# GAT262_LoRa_OTG.net
KiCad netlist of a schematic drawn in Altium Designer
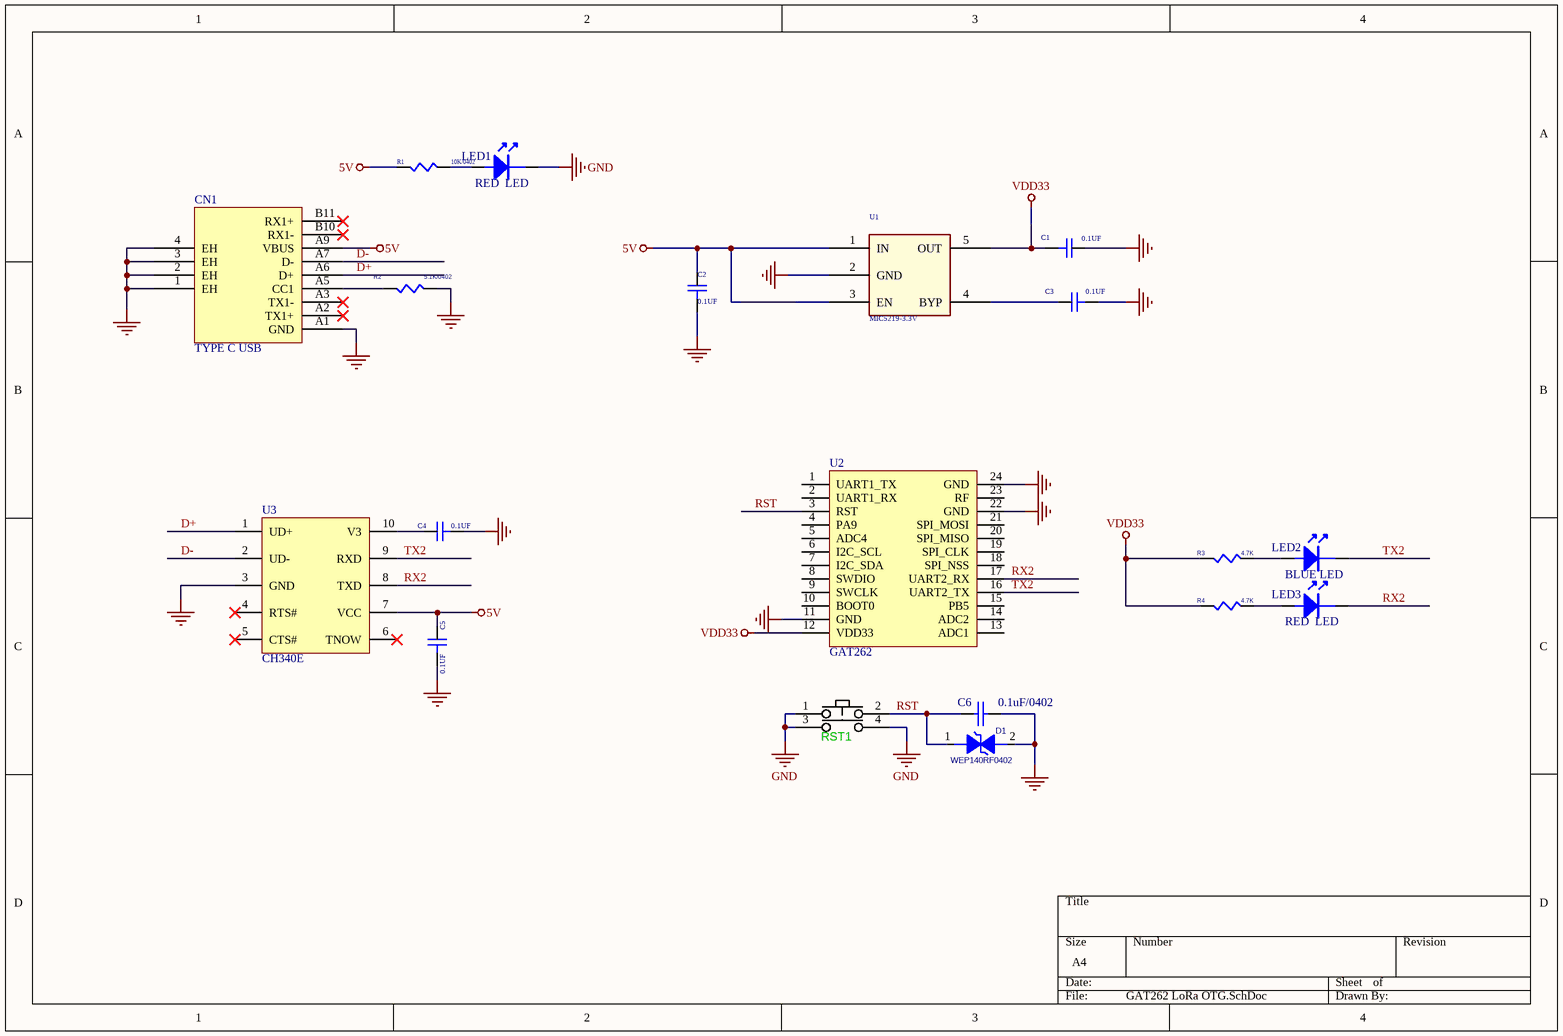
[diagram p0: GAT262 LoRa OTG.SchDoc]

(export (version "E")
  (design (tool "Eeschema 10.0.6"))
  (components
    (comp (ref "C1") (value "0.1UF") (footprint "C0402") (libsource (lib "*") (part "0_1.1UF")))
    (comp (ref "C2") (value "0.1UF") (footprint "C0402") (libsource (lib "*") (part "0_1.1UF")))
    (comp (ref "C3") (value "0.1UF") (footprint "C0402") (libsource (lib "*") (part "0_1.1UF")))
    (comp (ref "C4") (value "0.1UF") (footprint "C0402") (libsource (lib "*") (part "0_1.1UF")))
    (comp (ref "C5") (value "0.1UF") (footprint "C0402") (libsource (lib "*") (part "0_1.1UF")))
    (comp (ref "C6")
      (value "0.1uF/0402")
      (footprint "C0402")
      (description "Capacitor")
      (libsource (lib "电阻容感类") (part "CAP"))
    )
    (comp (ref "CN1")
      (value "TYPE C USB")
      (footprint "TYPE-C-9")
      (description "Type-C C2988371")
      (libsource (lib "Schlib1") (part "TYPE-C 9P"))
    )
    (comp (ref "D1")
      (value "WEP140RF0402")
      (footprint "ESD0402")
      (libsource (lib "*") (part "DIODE SCHOTTKY_1"))
    )
    (comp (ref "LED1")
      (value "RED  LED")
      (footprint "LED0603_RED_3D")
      (libsource (lib "LoRa DTU_20180911") (part "LED"))
    )
    (comp (ref "LED2")
      (value "BLUE LED")
      (footprint "LED0603_RED_3D")
      (libsource (lib "LoRa DTU_20180911") (part "LED"))
    )
    (comp (ref "LED3")
      (value "RED  LED")
      (footprint "LED0603_RED_3D")
      (libsource (lib "LoRa DTU_20180911") (part "LED"))
    )
    (comp (ref "R1") (value "10K/0402") (footprint "R0402") (libsource (lib "*") (part "R0402_1.06K_WALSIN")))
    (comp (ref "R2")
      (value "5.1K/0402")
      (footprint "R0402")
      (libsource (lib "*") (part "R0402_1.06K_WALSIN"))
    )
    (comp (ref "R3") (value "4.7K") (footprint "R0402") (libsource (lib "*") (part "R0402_1.06K_WALSIN")))
    (comp (ref "R4") (value "4.7K") (footprint "R0402") (libsource (lib "*") (part "R0402_1.06K_WALSIN")))
    (comp (ref "RST1") (value "KEY1") (footprint "SMDPUSHBUTTON4X2X3_5") (libsource (lib "*") (part "KEY1")))
    (comp (ref "U1")
      (value "MIC5219-3.3V")
      (footprint "SOT23-5")
      (libsource (lib "*") (part "REG CAT7101_2"))
    )
    (comp (ref "U2")
      (value "GAT262")
      (footprint "EVBCB-2*1.27")
      (description "2*12-1.2")
      (libsource (lib "STM32WLE5CC") (part "CONNECT_2"))
    )
    (comp (ref "U3") (value "CH340E") (footprint "CH340E") (libsource (lib "ST50H_EKB") (part "CH340E")))
  )
  (nets
    (net (code "1") (name "/D+") (class "Default")
      (node (ref "CN1") (pin "A6") (pinfunction "D+_A6") (pintype "passive"))
      (node (ref "U3") (pin "1") (pinfunction "UD+_1") (pintype "passive"))
    )
    (net (code "2") (name "/D-") (class "Default")
      (node (ref "CN1") (pin "A7") (pinfunction "D-_A7") (pintype "passive"))
      (node (ref "U3") (pin "2") (pinfunction "UD-_2") (pintype "passive"))
    )
    (net (code "3") (name "/RST") (class "Default")
      (node (ref "C6") (pin "2") (pinfunction "2_2") (pintype "passive"))
      (node (ref "D1") (pin "1") (pinfunction "ANODE_1") (pintype "passive"))
      (node (ref "RST1") (pin "2") (pinfunction "2_2") (pintype "passive"))
      (node (ref "U2") (pin "3") (pinfunction "RST_3") (pintype "passive"))
    )
    (net (code "4") (name "/RX2") (class "Default")
      (node (ref "LED3") (pin "2") (pinfunction "2_2") (pintype "passive"))
      (node (ref "U2") (pin "17") (pinfunction "UART2_RX_17") (pintype "passive"))
      (node (ref "U3") (pin "8") (pinfunction "TXD_8") (pintype "passive"))
    )
    (net (code "5") (name "/TX2") (class "Default")
      (node (ref "LED2") (pin "2") (pinfunction "2_2") (pintype "passive"))
      (node (ref "U2") (pin "16") (pinfunction "UART2_TX_16") (pintype "passive"))
      (node (ref "U3") (pin "9") (pinfunction "RXD_9") (pintype "passive"))
    )
    (net (code "6") (name "5V") (class "Default")
      (node (ref "C2") (pin "1") (pinfunction "1_1") (pintype "passive"))
      (node (ref "C5") (pin "1") (pinfunction "1_1") (pintype "passive"))
      (node (ref "CN1") (pin "A9") (pinfunction "VBUS_A9") (pintype "passive"))
      (node (ref "R1") (pin "2") (pinfunction "2_2") (pintype "passive"))
      (node (ref "U1") (pin "1") (pinfunction "IN_1") (pintype "passive"))
      (node (ref "U1") (pin "3") (pinfunction "EN_3") (pintype "passive"))
      (node (ref "U3") (pin "7") (pinfunction "VCC_7") (pintype "passive"))
    )
    (net (code "7") (name "GND") (class "Default")
      (node (ref "C1") (pin "1") (pinfunction "1_1") (pintype "passive"))
      (node (ref "C2") (pin "2") (pinfunction "2_2") (pintype "passive"))
      (node (ref "C3") (pin "2") (pinfunction "2_2") (pintype "passive"))
      (node (ref "C4") (pin "2") (pinfunction "2_2") (pintype "passive"))
      (node (ref "C5") (pin "2") (pinfunction "2_2") (pintype "passive"))
      (node (ref "C6") (pin "1") (pinfunction "1_1") (pintype "passive"))
      (node (ref "CN1") (pin "1") (pinfunction "EH_1") (pintype "passive"))
      (node (ref "CN1") (pin "2") (pinfunction "EH_2") (pintype "passive"))
      (node (ref "CN1") (pin "3") (pinfunction "EH_3") (pintype "passive"))
      (node (ref "CN1") (pin "4") (pinfunction "EH_4") (pintype "passive"))
      (node (ref "CN1") (pin "A1") (pinfunction "GND_A1") (pintype "passive"))
      (node (ref "D1") (pin "2") (pinfunction "CATHODE_2") (pintype "passive"))
      (node (ref "LED1") (pin "2") (pinfunction "2_2") (pintype "passive"))
      (node (ref "R2") (pin "2") (pinfunction "2_2") (pintype "passive"))
      (node (ref "RST1") (pin "1") (pinfunction "1_1") (pintype "passive"))
      (node (ref "RST1") (pin "3") (pinfunction "3_3") (pintype "passive"))
      (node (ref "RST1") (pin "4") (pinfunction "4_4") (pintype "passive"))
      (node (ref "U1") (pin "2") (pinfunction "GND_2") (pintype "passive"))
      (node (ref "U2") (pin "11") (pinfunction "GND_11") (pintype "passive"))
      (node (ref "U2") (pin "22") (pinfunction "GND_22") (pintype "passive"))
      (node (ref "U2") (pin "24") (pinfunction "GND_24") (pintype "passive"))
      (node (ref "U3") (pin "3") (pinfunction "GND_3") (pintype "passive"))
    )
    (net (code "8") (name "Net-(CN1-CC1)") (class "Default")
      (node (ref "CN1") (pin "A5") (pinfunction "CC1_A5") (pintype "passive"))
      (node (ref "R2") (pin "1") (pinfunction "1_1") (pintype "passive"))
    )
    (net (code "9") (name "Net-(LED1-Pad1)") (class "Default")
      (node (ref "LED1") (pin "1") (pinfunction "1_1") (pintype "passive"))
      (node (ref "R1") (pin "1") (pinfunction "1_1") (pintype "passive"))
    )
    (net (code "10") (name "Net-(LED2-Pad1)") (class "Default")
      (node (ref "LED2") (pin "1") (pinfunction "1_1") (pintype "passive"))
      (node (ref "R3") (pin "2") (pinfunction "2_2") (pintype "passive"))
    )
    (net (code "11") (name "Net-(LED3-Pad1)") (class "Default")
      (node (ref "LED3") (pin "1") (pinfunction "1_1") (pintype "passive"))
      (node (ref "R4") (pin "2") (pinfunction "2_2") (pintype "passive"))
    )
    (net (code "12") (name "Net-(U1-BYP)") (class "Default")
      (node (ref "C3") (pin "1") (pinfunction "1_1") (pintype "passive"))
      (node (ref "U1") (pin "4") (pinfunction "BYP_4") (pintype "passive"))
    )
    (net (code "13") (name "Net-(U3-V3)") (class "Default")
      (node (ref "C4") (pin "1") (pinfunction "1_1") (pintype "passive"))
      (node (ref "U3") (pin "10") (pinfunction "V3_10") (pintype "passive"))
    )
    (net (code "14") (name "VDD33") (class "Default")
      (node (ref "C1") (pin "2") (pinfunction "2_2") (pintype "passive"))
      (node (ref "R3") (pin "1") (pinfunction "1_1") (pintype "passive"))
      (node (ref "R4") (pin "1") (pinfunction "1_1") (pintype "passive"))
      (node (ref "U1") (pin "5") (pinfunction "OUT_5") (pintype "passive"))
      (node (ref "U2") (pin "12") (pinfunction "VDD33_12") (pintype "passive"))
    )
    (net (code "15") (name "unconnected-(CN1-RX1+-PadB11)") (class "Default")
      (node (ref "CN1") (pin "B11") (pinfunction "RX1+_B11") (pintype "passive+no_connect"))
    )
    (net (code "16") (name "unconnected-(CN1-RX1--PadB10)") (class "Default")
      (node (ref "CN1") (pin "B10") (pinfunction "RX1-_B10") (pintype "passive+no_connect"))
    )
    (net (code "17") (name "unconnected-(CN1-TX1+-PadA2)") (class "Default")
      (node (ref "CN1") (pin "A2") (pinfunction "TX1+_A2") (pintype "passive+no_connect"))
    )
    (net (code "18") (name "unconnected-(CN1-TX1--PadA3)") (class "Default")
      (node (ref "CN1") (pin "A3") (pinfunction "TX1-_A3") (pintype "passive+no_connect"))
    )
    (net (code "19") (name "unconnected-(U2-ADC1-Pad13)") (class "Default")
      (node (ref "U2") (pin "13") (pinfunction "ADC1_13") (pintype "passive"))
    )
    (net (code "20") (name "unconnected-(U2-ADC2-Pad14)") (class "Default")
      (node (ref "U2") (pin "14") (pinfunction "ADC2_14") (pintype "passive"))
    )
    (net (code "21") (name "unconnected-(U2-ADC4-Pad5)") (class "Default")
      (node (ref "U2") (pin "5") (pinfunction "ADC4_5") (pintype "passive"))
    )
    (net (code "22") (name "unconnected-(U2-BOOT0-Pad10)") (class "Default")
      (node (ref "U2") (pin "10") (pinfunction "BOOT0_10") (pintype "passive"))
    )
    (net (code "23") (name "unconnected-(U2-I2C_SCL-Pad6)") (class "Default")
      (node (ref "U2") (pin "6") (pinfunction "I2C_SCL_6") (pintype "passive"))
    )
    (net (code "24") (name "unconnected-(U2-I2C_SDA-Pad7)") (class "Default")
      (node (ref "U2") (pin "7") (pinfunction "I2C_SDA_7") (pintype "passive"))
    )
    (net (code "25") (name "unconnected-(U2-PA9-Pad4)") (class "Default")
      (node (ref "U2") (pin "4") (pinfunction "PA9_4") (pintype "passive"))
    )
    (net (code "26") (name "unconnected-(U2-PB5-Pad15)") (class "Default")
      (node (ref "U2") (pin "15") (pinfunction "PB5_15") (pintype "passive"))
    )
    (net (code "27") (name "unconnected-(U2-RF-Pad23)") (class "Default")
      (node (ref "U2") (pin "23") (pinfunction "RF_23") (pintype "passive"))
    )
    (net (code "28") (name "unconnected-(U2-SPI_CLK-Pad19)") (class "Default")
      (node (ref "U2") (pin "19") (pinfunction "SPI_CLK_19") (pintype "passive"))
    )
    (net (code "29") (name "unconnected-(U2-SPI_MISO-Pad20)") (class "Default")
      (node (ref "U2") (pin "20") (pinfunction "SPI_MISO_20") (pintype "passive"))
    )
    (net (code "30") (name "unconnected-(U2-SPI_MOSI-Pad21)") (class "Default")
      (node (ref "U2") (pin "21") (pinfunction "SPI_MOSI_21") (pintype "passive"))
    )
    (net (code "31") (name "unconnected-(U2-SPI_NSS-Pad18)") (class "Default")
      (node (ref "U2") (pin "18") (pinfunction "SPI_NSS_18") (pintype "passive"))
    )
    (net (code "32") (name "unconnected-(U2-SWCLK-Pad9)") (class "Default")
      (node (ref "U2") (pin "9") (pinfunction "SWCLK_9") (pintype "passive"))
    )
    (net (code "33") (name "unconnected-(U2-SWDIO-Pad8)") (class "Default")
      (node (ref "U2") (pin "8") (pinfunction "SWDIO_8") (pintype "passive"))
    )
    (net (code "34") (name "unconnected-(U2-UART1_RX-Pad2)") (class "Default")
      (node (ref "U2") (pin "2") (pinfunction "UART1_RX_2") (pintype "passive"))
    )
    (net (code "35") (name "unconnected-(U2-UART1_TX-Pad1)") (class "Default")
      (node (ref "U2") (pin "1") (pinfunction "UART1_TX_1") (pintype "passive"))
    )
    (net (code "36") (name "unconnected-(U3-CTS#-Pad5)") (class "Default")
      (node (ref "U3") (pin "5") (pinfunction "CTS#_5") (pintype "passive+no_connect"))
    )
    (net (code "37") (name "unconnected-(U3-RTS#-Pad4)") (class "Default")
      (node (ref "U3") (pin "4") (pinfunction "RTS#_4") (pintype "passive+no_connect"))
    )
    (net (code "38") (name "unconnected-(U3-TNOW-Pad6)") (class "Default")
      (node (ref "U3") (pin "6") (pinfunction "TNOW_6") (pintype "passive+no_connect"))
    )
  )
)
